# working.net
KiCad netlist of a schematic drawn in EAGLE
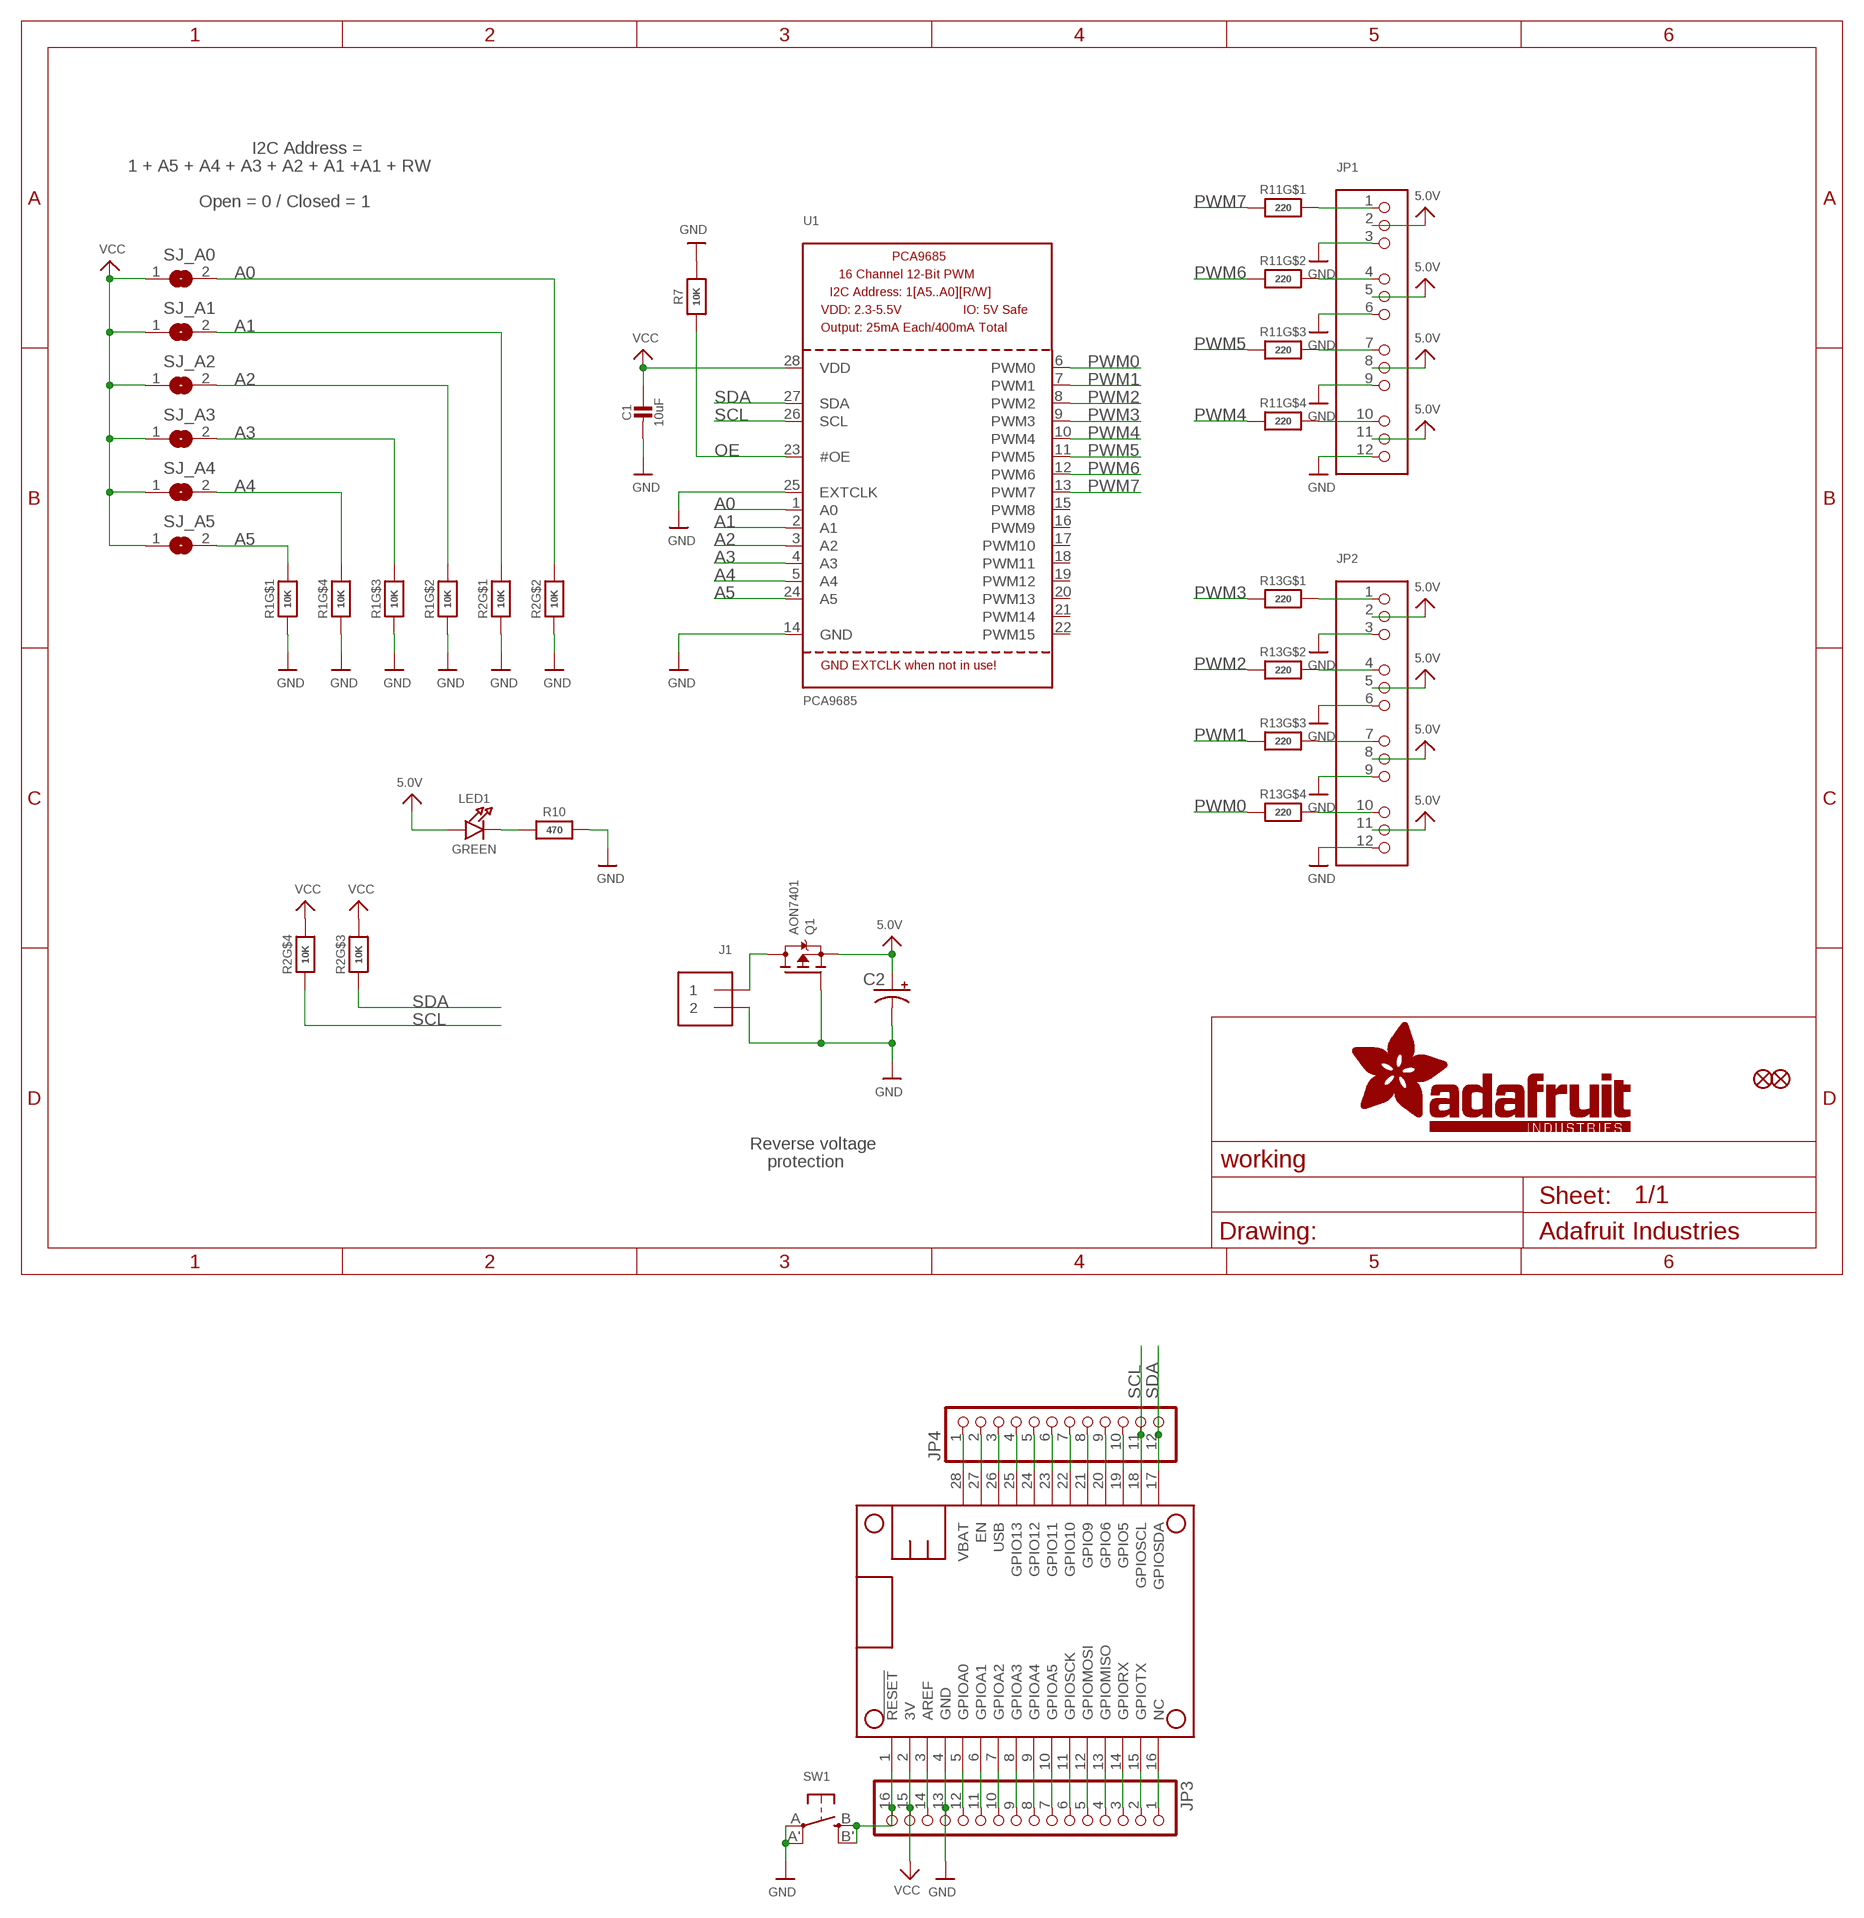
[diagram p0: schematic, sheet 1]

(export (version "E")
  (design (tool "Eeschema 10.0.6"))
  (components
    (comp (ref "C1")
      (value "10uF")
      (footprint "eagle-import:0805-NO")
      (libsource (lib "eagle-import") (part "CAP_CERAMIC0805-NOOUTLINE"))
    )
    (comp (ref "C2")
      (value "CPOL-USE3.5-8")
      (footprint "eagle-import:E3,5-8")
      (libsource (lib "eagle-import") (part "CPOL-USE3.5-8"))
    )
    (comp (ref "FID1")
      (value "FIDUCIAL\"\"")
      (footprint "eagle-import:FIDUCIAL_1MM")
      (libsource (lib "eagle-import") (part "FIDUCIAL{dblquote}{dblquote}"))
    )
    (comp (ref "FID2")
      (value "FIDUCIAL\"\"")
      (footprint "eagle-import:FIDUCIAL_1MM")
      (libsource (lib "eagle-import") (part "FIDUCIAL{dblquote}{dblquote}"))
    )
    (comp (ref "J1")
      (value "TERMBLOCK_1X2")
      (footprint "eagle-import:TERMBLOCK_1X2-3.5MM")
      (libsource (lib "eagle-import") (part "TERMBLOCK_1X2"))
    )
    (comp (ref "JP1")
      (value "HEADER-3X04")
      (footprint "eagle-import:3X04")
      (libsource (lib "eagle-import") (part "HEADER-3X04"))
    )
    (comp (ref "JP2")
      (value "HEADER-3X04")
      (footprint "eagle-import:3X04")
      (libsource (lib "eagle-import") (part "HEADER-3X04"))
    )
    (comp (ref "JP3")
      (value "HEADER-1X16ROUND")
      (footprint "eagle-import:1X16_ROUND")
      (libsource (lib "eagle-import") (part "HEADER-1X16ROUND"))
    )
    (comp (ref "JP4")
      (value "HEADER-1X12")
      (footprint "eagle-import:1X12_ROUND")
      (libsource (lib "eagle-import") (part "HEADER-1X12"))
    )
    (comp (ref "LED1")
      (value "GREEN")
      (footprint "eagle-import:CHIPLED_0805_NOOUTLINE")
      (libsource (lib "eagle-import") (part "LED0805_NOOUTLINE"))
    )
    (comp (ref "MS1")
      (value "FEATHERWING")
      (footprint "eagle-import:FEATHERWING")
      (libsource (lib "eagle-import") (part "FEATHERWING"))
    )
    (comp (ref "Q1")
      (value "AON7401")
      (footprint "eagle-import:POWERDI3333")
      (libsource (lib "eagle-import") (part "MOSFET-P-POWERDI3333"))
    )
    (comp (ref "R1")
      (value "10K")
      (footprint "eagle-import:RESPACK_4X0603")
      (libsource (lib "eagle-import") (part "RESISTOR_4PACK"))
    )
    (comp (ref "R2")
      (value "10K")
      (footprint "eagle-import:RESPACK_4X0603")
      (libsource (lib "eagle-import") (part "RESISTOR_4PACK"))
    )
    (comp (ref "R7")
      (value "10K")
      (footprint "eagle-import:0805-NO")
      (libsource (lib "eagle-import") (part "RESISTOR0805_NOOUTLINE"))
    )
    (comp (ref "R10")
      (value "470")
      (footprint "eagle-import:0805-NO")
      (libsource (lib "eagle-import") (part "RESISTOR0805_NOOUTLINE"))
    )
    (comp (ref "R11")
      (value "220")
      (footprint "eagle-import:RESPACK_4X0603")
      (libsource (lib "eagle-import") (part "RESISTOR_4PACK"))
    )
    (comp (ref "R13")
      (value "220")
      (footprint "eagle-import:RESPACK_4X0603")
      (libsource (lib "eagle-import") (part "RESISTOR_4PACK"))
    )
    (comp (ref "SJ_A0")
      (value "SOLDERJUMPERREFLOW_NOPASTE")
      (footprint "eagle-import:SOLDERJUMPER_REFLOW_NOPASTE")
      (libsource (lib "eagle-import") (part "SOLDERJUMPERREFLOW_NOPASTE"))
    )
    (comp (ref "SJ_A1")
      (value "SOLDERJUMPERREFLOW_NOPASTE")
      (footprint "eagle-import:SOLDERJUMPER_REFLOW_NOPASTE")
      (libsource (lib "eagle-import") (part "SOLDERJUMPERREFLOW_NOPASTE"))
    )
    (comp (ref "SJ_A2")
      (value "SOLDERJUMPERREFLOW_NOPASTE")
      (footprint "eagle-import:SOLDERJUMPER_REFLOW_NOPASTE")
      (libsource (lib "eagle-import") (part "SOLDERJUMPERREFLOW_NOPASTE"))
    )
    (comp (ref "SJ_A3")
      (value "SOLDERJUMPERREFLOW_NOPASTE")
      (footprint "eagle-import:SOLDERJUMPER_REFLOW_NOPASTE")
      (libsource (lib "eagle-import") (part "SOLDERJUMPERREFLOW_NOPASTE"))
    )
    (comp (ref "SJ_A4")
      (value "SOLDERJUMPERREFLOW_NOPASTE")
      (footprint "eagle-import:SOLDERJUMPER_REFLOW_NOPASTE")
      (libsource (lib "eagle-import") (part "SOLDERJUMPERREFLOW_NOPASTE"))
    )
    (comp (ref "SJ_A5")
      (value "SOLDERJUMPERREFLOW_NOPASTE")
      (footprint "eagle-import:SOLDERJUMPER_REFLOW_NOPASTE")
      (libsource (lib "eagle-import") (part "SOLDERJUMPERREFLOW_NOPASTE"))
    )
    (comp (ref "SW1")
      (value "SWITCH_TACT_SMT4.6X2.8")
      (footprint "eagle-import:BTN_KMR2_4.6X2.8")
      (libsource (lib "eagle-import") (part "SWITCH_TACT_SMT4.6X2.8"))
    )
    (comp (ref "U1")
      (value "PCA9685")
      (footprint "eagle-import:TSSOP28")
      (libsource (lib "eagle-import") (part "PCA9685"))
    )
  )
  (nets
    (net (code "1") (name "/A0") (class "Default")
      (node (ref "R2") (pin "7") (pinfunction "2_7") (pintype "passive"))
      (node (ref "SJ_A0") (pin "2") (pinfunction "2_2") (pintype "passive"))
      (node (ref "U1") (pin "1") (pinfunction "A0_1") (pintype "bidirectional"))
    )
    (net (code "2") (name "/A1") (class "Default")
      (node (ref "R2") (pin "8") (pinfunction "2_8") (pintype "passive"))
      (node (ref "SJ_A1") (pin "2") (pinfunction "2_2") (pintype "passive"))
      (node (ref "U1") (pin "2") (pinfunction "A1_2") (pintype "bidirectional"))
    )
    (net (code "3") (name "/A2") (class "Default")
      (node (ref "R1") (pin "7") (pinfunction "2_7") (pintype "passive"))
      (node (ref "SJ_A2") (pin "2") (pinfunction "2_2") (pintype "passive"))
      (node (ref "U1") (pin "3") (pinfunction "A2_3") (pintype "bidirectional"))
    )
    (net (code "4") (name "/A3") (class "Default")
      (node (ref "R1") (pin "6") (pinfunction "2_6") (pintype "passive"))
      (node (ref "SJ_A3") (pin "2") (pinfunction "2_2") (pintype "passive"))
      (node (ref "U1") (pin "4") (pinfunction "A3_4") (pintype "bidirectional"))
    )
    (net (code "5") (name "/A4") (class "Default")
      (node (ref "R1") (pin "5") (pinfunction "2_5") (pintype "passive"))
      (node (ref "SJ_A4") (pin "2") (pinfunction "2_2") (pintype "passive"))
      (node (ref "U1") (pin "5") (pinfunction "A4_5") (pintype "bidirectional"))
    )
    (net (code "6") (name "/A5") (class "Default")
      (node (ref "R1") (pin "8") (pinfunction "2_8") (pintype "passive"))
      (node (ref "SJ_A5") (pin "2") (pinfunction "2_2") (pintype "passive"))
      (node (ref "U1") (pin "24") (pinfunction "A5_24") (pintype "bidirectional"))
    )
    (net (code "7") (name "/OE") (class "Default")
      (node (ref "R7") (pin "1") (pinfunction "1_1") (pintype "passive"))
      (node (ref "U1") (pin "23") (pinfunction "#OE_23") (pintype "input"))
    )
    (net (code "8") (name "/PWM0") (class "Default")
      (node (ref "R13") (pin "4") (pinfunction "1_4") (pintype "passive"))
      (node (ref "U1") (pin "6") (pinfunction "PWM0_6") (pintype "output"))
    )
    (net (code "9") (name "/PWM1") (class "Default")
      (node (ref "R13") (pin "3") (pinfunction "1_3") (pintype "passive"))
      (node (ref "U1") (pin "7") (pinfunction "PWM1_7") (pintype "output"))
    )
    (net (code "10") (name "/PWM2") (class "Default")
      (node (ref "R13") (pin "2") (pinfunction "1_2") (pintype "passive"))
      (node (ref "U1") (pin "8") (pinfunction "PWM2_8") (pintype "output"))
    )
    (net (code "11") (name "/PWM3") (class "Default")
      (node (ref "R13") (pin "1") (pinfunction "1_1") (pintype "passive"))
      (node (ref "U1") (pin "9") (pinfunction "PWM3_9") (pintype "output"))
    )
    (net (code "12") (name "/PWM4") (class "Default")
      (node (ref "R11") (pin "4") (pinfunction "1_4") (pintype "passive"))
      (node (ref "U1") (pin "10") (pinfunction "PWM4_10") (pintype "output"))
    )
    (net (code "13") (name "/PWM5") (class "Default")
      (node (ref "R11") (pin "3") (pinfunction "1_3") (pintype "passive"))
      (node (ref "U1") (pin "11") (pinfunction "PWM5_11") (pintype "output"))
    )
    (net (code "14") (name "/PWM6") (class "Default")
      (node (ref "R11") (pin "2") (pinfunction "1_2") (pintype "passive"))
      (node (ref "U1") (pin "12") (pinfunction "PWM6_12") (pintype "output"))
    )
    (net (code "15") (name "/PWM7") (class "Default")
      (node (ref "R11") (pin "1") (pinfunction "1_1") (pintype "passive"))
      (node (ref "U1") (pin "13") (pinfunction "PWM7_13") (pintype "output"))
    )
    (net (code "16") (name "/SCL") (class "Default")
      (node (ref "JP4") (pin "11") (pinfunction "11_11") (pintype "passive"))
      (node (ref "MS1") (pin "18") (pinfunction "GPIOSCL_18") (pintype "bidirectional"))
      (node (ref "R2") (pin "4") (pinfunction "1_4") (pintype "passive"))
      (node (ref "U1") (pin "26") (pinfunction "SCL_26") (pintype "bidirectional"))
    )
    (net (code "17") (name "/SDA") (class "Default")
      (node (ref "JP4") (pin "12") (pinfunction "12_12") (pintype "passive"))
      (node (ref "MS1") (pin "17") (pinfunction "GPIOSDA_17") (pintype "bidirectional"))
      (node (ref "R2") (pin "3") (pinfunction "1_3") (pintype "passive"))
      (node (ref "U1") (pin "27") (pinfunction "SDA_27") (pintype "bidirectional"))
    )
    (net (code "18") (name "5.0V") (class "Default")
      (node (ref "C2") (pin "+") (pinfunction "+_+") (pintype "passive"))
      (node (ref "JP1") (pin "11") (pinfunction "11_11") (pintype "passive"))
      (node (ref "JP1") (pin "2") (pinfunction "2_2") (pintype "passive"))
      (node (ref "JP1") (pin "5") (pinfunction "5_5") (pintype "passive"))
      (node (ref "JP1") (pin "8") (pinfunction "8_8") (pintype "passive"))
      (node (ref "JP2") (pin "11") (pinfunction "11_11") (pintype "passive"))
      (node (ref "JP2") (pin "2") (pinfunction "2_2") (pintype "passive"))
      (node (ref "JP2") (pin "5") (pinfunction "5_5") (pintype "passive"))
      (node (ref "JP2") (pin "8") (pinfunction "8_8") (pintype "passive"))
      (node (ref "LED1") (pin "A") (pinfunction "A_A") (pintype "passive"))
      (node (ref "Q1") (pin "1") (pinfunction "S_1") (pintype "passive"))
      (node (ref "Q1") (pin "2") (pinfunction "S_2") (pintype "passive"))
      (node (ref "Q1") (pin "3") (pinfunction "S_3") (pintype "passive"))
    )
    (net (code "19") (name "GND") (class "Default")
      (node (ref "C1") (pin "2") (pinfunction "2_2") (pintype "passive"))
      (node (ref "C2") (pin "-") (pinfunction "-_-") (pintype "passive"))
      (node (ref "J1") (pin "2") (pinfunction "2_2") (pintype "passive"))
      (node (ref "JP1") (pin "12") (pinfunction "12_12") (pintype "passive"))
      (node (ref "JP1") (pin "3") (pinfunction "3_3") (pintype "passive"))
      (node (ref "JP1") (pin "6") (pinfunction "6_6") (pintype "passive"))
      (node (ref "JP1") (pin "9") (pinfunction "9_9") (pintype "passive"))
      (node (ref "JP2") (pin "12") (pinfunction "12_12") (pintype "passive"))
      (node (ref "JP2") (pin "3") (pinfunction "3_3") (pintype "passive"))
      (node (ref "JP2") (pin "6") (pinfunction "6_6") (pintype "passive"))
      (node (ref "JP2") (pin "9") (pinfunction "9_9") (pintype "passive"))
      (node (ref "JP3") (pin "13") (pinfunction "13_13") (pintype "passive"))
      (node (ref "MS1") (pin "4") (pinfunction "GND_4") (pintype "power_in"))
      (node (ref "Q1") (pin "4") (pinfunction "G_4") (pintype "passive"))
      (node (ref "R1") (pin "1") (pinfunction "1_1") (pintype "passive"))
      (node (ref "R1") (pin "2") (pinfunction "1_2") (pintype "passive"))
      (node (ref "R1") (pin "3") (pinfunction "1_3") (pintype "passive"))
      (node (ref "R1") (pin "4") (pinfunction "1_4") (pintype "passive"))
      (node (ref "R10") (pin "2") (pinfunction "2_2") (pintype "passive"))
      (node (ref "R2") (pin "1") (pinfunction "1_1") (pintype "passive"))
      (node (ref "R2") (pin "2") (pinfunction "1_2") (pintype "passive"))
      (node (ref "R7") (pin "2") (pinfunction "2_2") (pintype "passive"))
      (node (ref "SW1") (pin "A") (pinfunction "P_A") (pintype "passive"))
      (node (ref "SW1") (pin "A'") (pinfunction "P1_A'") (pintype "passive"))
      (node (ref "U1") (pin "14") (pinfunction "GND_14") (pintype "power_in"))
      (node (ref "U1") (pin "25") (pinfunction "EXTCLK_25") (pintype "input"))
    )
    (net (code "20") (name "Net-(LED1-PadC)") (class "Default")
      (node (ref "LED1") (pin "C") (pinfunction "C_C") (pintype "passive"))
      (node (ref "R10") (pin "1") (pinfunction "1_1") (pintype "passive"))
    )
    (net (code "21") (name "Net-(MS1-AREF)") (class "Default")
      (node (ref "JP3") (pin "14") (pinfunction "14_14") (pintype "passive"))
      (node (ref "MS1") (pin "3") (pinfunction "AREF_3") (pintype "passive"))
    )
    (net (code "22") (name "Net-(MS1-EN)") (class "Default")
      (node (ref "JP4") (pin "2") (pinfunction "2_2") (pintype "passive"))
      (node (ref "MS1") (pin "27") (pinfunction "EN_27") (pintype "passive"))
    )
    (net (code "23") (name "Net-(MS1-GPIO5)") (class "Default")
      (node (ref "JP4") (pin "10") (pinfunction "10_10") (pintype "passive"))
      (node (ref "MS1") (pin "19") (pinfunction "GPIO5_19") (pintype "bidirectional"))
    )
    (net (code "24") (name "Net-(MS1-GPIO6)") (class "Default")
      (node (ref "JP4") (pin "9") (pinfunction "9_9") (pintype "passive"))
      (node (ref "MS1") (pin "20") (pinfunction "GPIO6_20") (pintype "bidirectional"))
    )
    (net (code "25") (name "Net-(MS1-GPIO9)") (class "Default")
      (node (ref "JP4") (pin "8") (pinfunction "8_8") (pintype "passive"))
      (node (ref "MS1") (pin "21") (pinfunction "GPIO9_21") (pintype "bidirectional"))
    )
    (net (code "26") (name "Net-(MS1-GPIO10)") (class "Default")
      (node (ref "JP4") (pin "7") (pinfunction "7_7") (pintype "passive"))
      (node (ref "MS1") (pin "22") (pinfunction "GPIO10_22") (pintype "bidirectional"))
    )
    (net (code "27") (name "Net-(MS1-GPIO11)") (class "Default")
      (node (ref "JP4") (pin "6") (pinfunction "6_6") (pintype "passive"))
      (node (ref "MS1") (pin "23") (pinfunction "GPIO11_23") (pintype "bidirectional"))
    )
    (net (code "28") (name "Net-(MS1-GPIO12)") (class "Default")
      (node (ref "JP4") (pin "5") (pinfunction "5_5") (pintype "passive"))
      (node (ref "MS1") (pin "24") (pinfunction "GPIO12_24") (pintype "bidirectional"))
    )
    (net (code "29") (name "Net-(MS1-GPIO13)") (class "Default")
      (node (ref "JP4") (pin "4") (pinfunction "4_4") (pintype "passive"))
      (node (ref "MS1") (pin "25") (pinfunction "GPIO13_25") (pintype "bidirectional"))
    )
    (net (code "30") (name "Net-(MS1-GPIOA0)") (class "Default")
      (node (ref "JP3") (pin "12") (pinfunction "12_12") (pintype "passive"))
      (node (ref "MS1") (pin "5") (pinfunction "GPIOA0_5") (pintype "bidirectional"))
    )
    (net (code "31") (name "Net-(MS1-GPIOA1)") (class "Default")
      (node (ref "JP3") (pin "11") (pinfunction "11_11") (pintype "passive"))
      (node (ref "MS1") (pin "6") (pinfunction "GPIOA1_6") (pintype "bidirectional"))
    )
    (net (code "32") (name "Net-(MS1-GPIOA2)") (class "Default")
      (node (ref "JP3") (pin "10") (pinfunction "10_10") (pintype "passive"))
      (node (ref "MS1") (pin "7") (pinfunction "GPIOA2_7") (pintype "bidirectional"))
    )
    (net (code "33") (name "Net-(MS1-GPIOA3)") (class "Default")
      (node (ref "JP3") (pin "9") (pinfunction "9_9") (pintype "passive"))
      (node (ref "MS1") (pin "8") (pinfunction "GPIOA3_8") (pintype "bidirectional"))
    )
    (net (code "34") (name "Net-(MS1-GPIOA4)") (class "Default")
      (node (ref "JP3") (pin "8") (pinfunction "8_8") (pintype "passive"))
      (node (ref "MS1") (pin "9") (pinfunction "GPIOA4_9") (pintype "bidirectional"))
    )
    (net (code "35") (name "Net-(MS1-GPIOA5)") (class "Default")
      (node (ref "JP3") (pin "7") (pinfunction "7_7") (pintype "passive"))
      (node (ref "MS1") (pin "10") (pinfunction "GPIOA5_10") (pintype "bidirectional"))
    )
    (net (code "36") (name "Net-(MS1-GPIOMISO)") (class "Default")
      (node (ref "JP3") (pin "4") (pinfunction "4_4") (pintype "passive"))
      (node (ref "MS1") (pin "13") (pinfunction "GPIOMISO_13") (pintype "bidirectional"))
    )
    (net (code "37") (name "Net-(MS1-GPIOMOSI)") (class "Default")
      (node (ref "JP3") (pin "5") (pinfunction "5_5") (pintype "passive"))
      (node (ref "MS1") (pin "12") (pinfunction "GPIOMOSI_12") (pintype "bidirectional"))
    )
    (net (code "38") (name "Net-(MS1-GPIORX)") (class "Default")
      (node (ref "JP3") (pin "3") (pinfunction "3_3") (pintype "passive"))
      (node (ref "MS1") (pin "14") (pinfunction "GPIORX_14") (pintype "bidirectional"))
    )
    (net (code "39") (name "Net-(MS1-GPIOSCK)") (class "Default")
      (node (ref "JP3") (pin "6") (pinfunction "6_6") (pintype "passive"))
      (node (ref "MS1") (pin "11") (pinfunction "GPIOSCK_11") (pintype "bidirectional"))
    )
    (net (code "40") (name "Net-(MS1-GPIOTX)") (class "Default")
      (node (ref "JP3") (pin "2") (pinfunction "2_2") (pintype "passive"))
      (node (ref "MS1") (pin "15") (pinfunction "GPIOTX_15") (pintype "bidirectional"))
    )
    (net (code "41") (name "Net-(MS1-NC)") (class "Default")
      (node (ref "JP3") (pin "1") (pinfunction "1_1") (pintype "passive"))
      (node (ref "MS1") (pin "16") (pinfunction "NC_16") (pintype "passive"))
    )
    (net (code "42") (name "Net-(MS1-USB)") (class "Default")
      (node (ref "JP4") (pin "3") (pinfunction "3_3") (pintype "passive"))
      (node (ref "MS1") (pin "26") (pinfunction "USB_26") (pintype "power_in"))
    )
    (net (code "43") (name "Net-(MS1-VBAT)") (class "Default")
      (node (ref "JP4") (pin "1") (pinfunction "1_1") (pintype "passive"))
      (node (ref "MS1") (pin "28") (pinfunction "VBAT_28") (pintype "power_in"))
    )
    (net (code "44") (name "Net-(MS1-~{RESET})") (class "Default")
      (node (ref "JP3") (pin "16") (pinfunction "16_16") (pintype "passive"))
      (node (ref "MS1") (pin "1") (pinfunction "~{RESET}_1") (pintype "input"))
      (node (ref "SW1") (pin "B") (pinfunction "S_B") (pintype "passive"))
      (node (ref "SW1") (pin "B'") (pinfunction "S1_B'") (pintype "passive"))
    )
    (net (code "45") (name "Net-(Q1-D)") (class "Default")
      (node (ref "J1") (pin "1") (pinfunction "1_1") (pintype "passive"))
      (node (ref "Q1") (pin "5678") (pinfunction "D_5678") (pintype "passive"))
    )
    (net (code "46") (name "Net-(R11A-2)") (class "Default")
      (node (ref "JP1") (pin "1") (pinfunction "1_1") (pintype "passive"))
      (node (ref "R11") (pin "8") (pinfunction "2_8") (pintype "passive"))
    )
    (net (code "47") (name "Net-(R11B-2)") (class "Default")
      (node (ref "JP1") (pin "4") (pinfunction "4_4") (pintype "passive"))
      (node (ref "R11") (pin "7") (pinfunction "2_7") (pintype "passive"))
    )
    (net (code "48") (name "Net-(R11C-2)") (class "Default")
      (node (ref "JP1") (pin "7") (pinfunction "7_7") (pintype "passive"))
      (node (ref "R11") (pin "6") (pinfunction "2_6") (pintype "passive"))
    )
    (net (code "49") (name "Net-(R11D-2)") (class "Default")
      (node (ref "JP1") (pin "10") (pinfunction "10_10") (pintype "passive"))
      (node (ref "R11") (pin "5") (pinfunction "2_5") (pintype "passive"))
    )
    (net (code "50") (name "Net-(R13A-2)") (class "Default")
      (node (ref "JP2") (pin "1") (pinfunction "1_1") (pintype "passive"))
      (node (ref "R13") (pin "8") (pinfunction "2_8") (pintype "passive"))
    )
    (net (code "51") (name "Net-(R13B-2)") (class "Default")
      (node (ref "JP2") (pin "4") (pinfunction "4_4") (pintype "passive"))
      (node (ref "R13") (pin "7") (pinfunction "2_7") (pintype "passive"))
    )
    (net (code "52") (name "Net-(R13C-2)") (class "Default")
      (node (ref "JP2") (pin "7") (pinfunction "7_7") (pintype "passive"))
      (node (ref "R13") (pin "6") (pinfunction "2_6") (pintype "passive"))
    )
    (net (code "53") (name "Net-(R13D-2)") (class "Default")
      (node (ref "JP2") (pin "10") (pinfunction "10_10") (pintype "passive"))
      (node (ref "R13") (pin "5") (pinfunction "2_5") (pintype "passive"))
    )
    (net (code "54") (name "VCC") (class "Default")
      (node (ref "C1") (pin "1") (pinfunction "1_1") (pintype "passive"))
      (node (ref "JP3") (pin "15") (pinfunction "15_15") (pintype "passive"))
      (node (ref "MS1") (pin "2") (pinfunction "3V_2") (pintype "power_in"))
      (node (ref "R2") (pin "5") (pinfunction "2_5") (pintype "passive"))
      (node (ref "R2") (pin "6") (pinfunction "2_6") (pintype "passive"))
      (node (ref "SJ_A0") (pin "1") (pinfunction "1_1") (pintype "passive"))
      (node (ref "SJ_A1") (pin "1") (pinfunction "1_1") (pintype "passive"))
      (node (ref "SJ_A2") (pin "1") (pinfunction "1_1") (pintype "passive"))
      (node (ref "SJ_A3") (pin "1") (pinfunction "1_1") (pintype "passive"))
      (node (ref "SJ_A4") (pin "1") (pinfunction "1_1") (pintype "passive"))
      (node (ref "SJ_A5") (pin "1") (pinfunction "1_1") (pintype "passive"))
      (node (ref "U1") (pin "28") (pinfunction "VDD_28") (pintype "power_in"))
    )
    (net (code "55") (name "unconnected-(U1-PWM8-Pad15)") (class "Default")
      (node (ref "U1") (pin "15") (pinfunction "PWM8_15") (pintype "output"))
    )
    (net (code "56") (name "unconnected-(U1-PWM9-Pad16)") (class "Default")
      (node (ref "U1") (pin "16") (pinfunction "PWM9_16") (pintype "output"))
    )
    (net (code "57") (name "unconnected-(U1-PWM10-Pad17)") (class "Default")
      (node (ref "U1") (pin "17") (pinfunction "PWM10_17") (pintype "output"))
    )
    (net (code "58") (name "unconnected-(U1-PWM11-Pad18)") (class "Default")
      (node (ref "U1") (pin "18") (pinfunction "PWM11_18") (pintype "output"))
    )
    (net (code "59") (name "unconnected-(U1-PWM12-Pad19)") (class "Default")
      (node (ref "U1") (pin "19") (pinfunction "PWM12_19") (pintype "output"))
    )
    (net (code "60") (name "unconnected-(U1-PWM13-Pad20)") (class "Default")
      (node (ref "U1") (pin "20") (pinfunction "PWM13_20") (pintype "output"))
    )
    (net (code "61") (name "unconnected-(U1-PWM14-Pad21)") (class "Default")
      (node (ref "U1") (pin "21") (pinfunction "PWM14_21") (pintype "output"))
    )
    (net (code "62") (name "unconnected-(U1-PWM15-Pad22)") (class "Default")
      (node (ref "U1") (pin "22") (pinfunction "PWM15_22") (pintype "output"))
    )
  )
)
